# AAA_Battery_Card.net
KiCad netlist of a schematic drawn in EAGLE
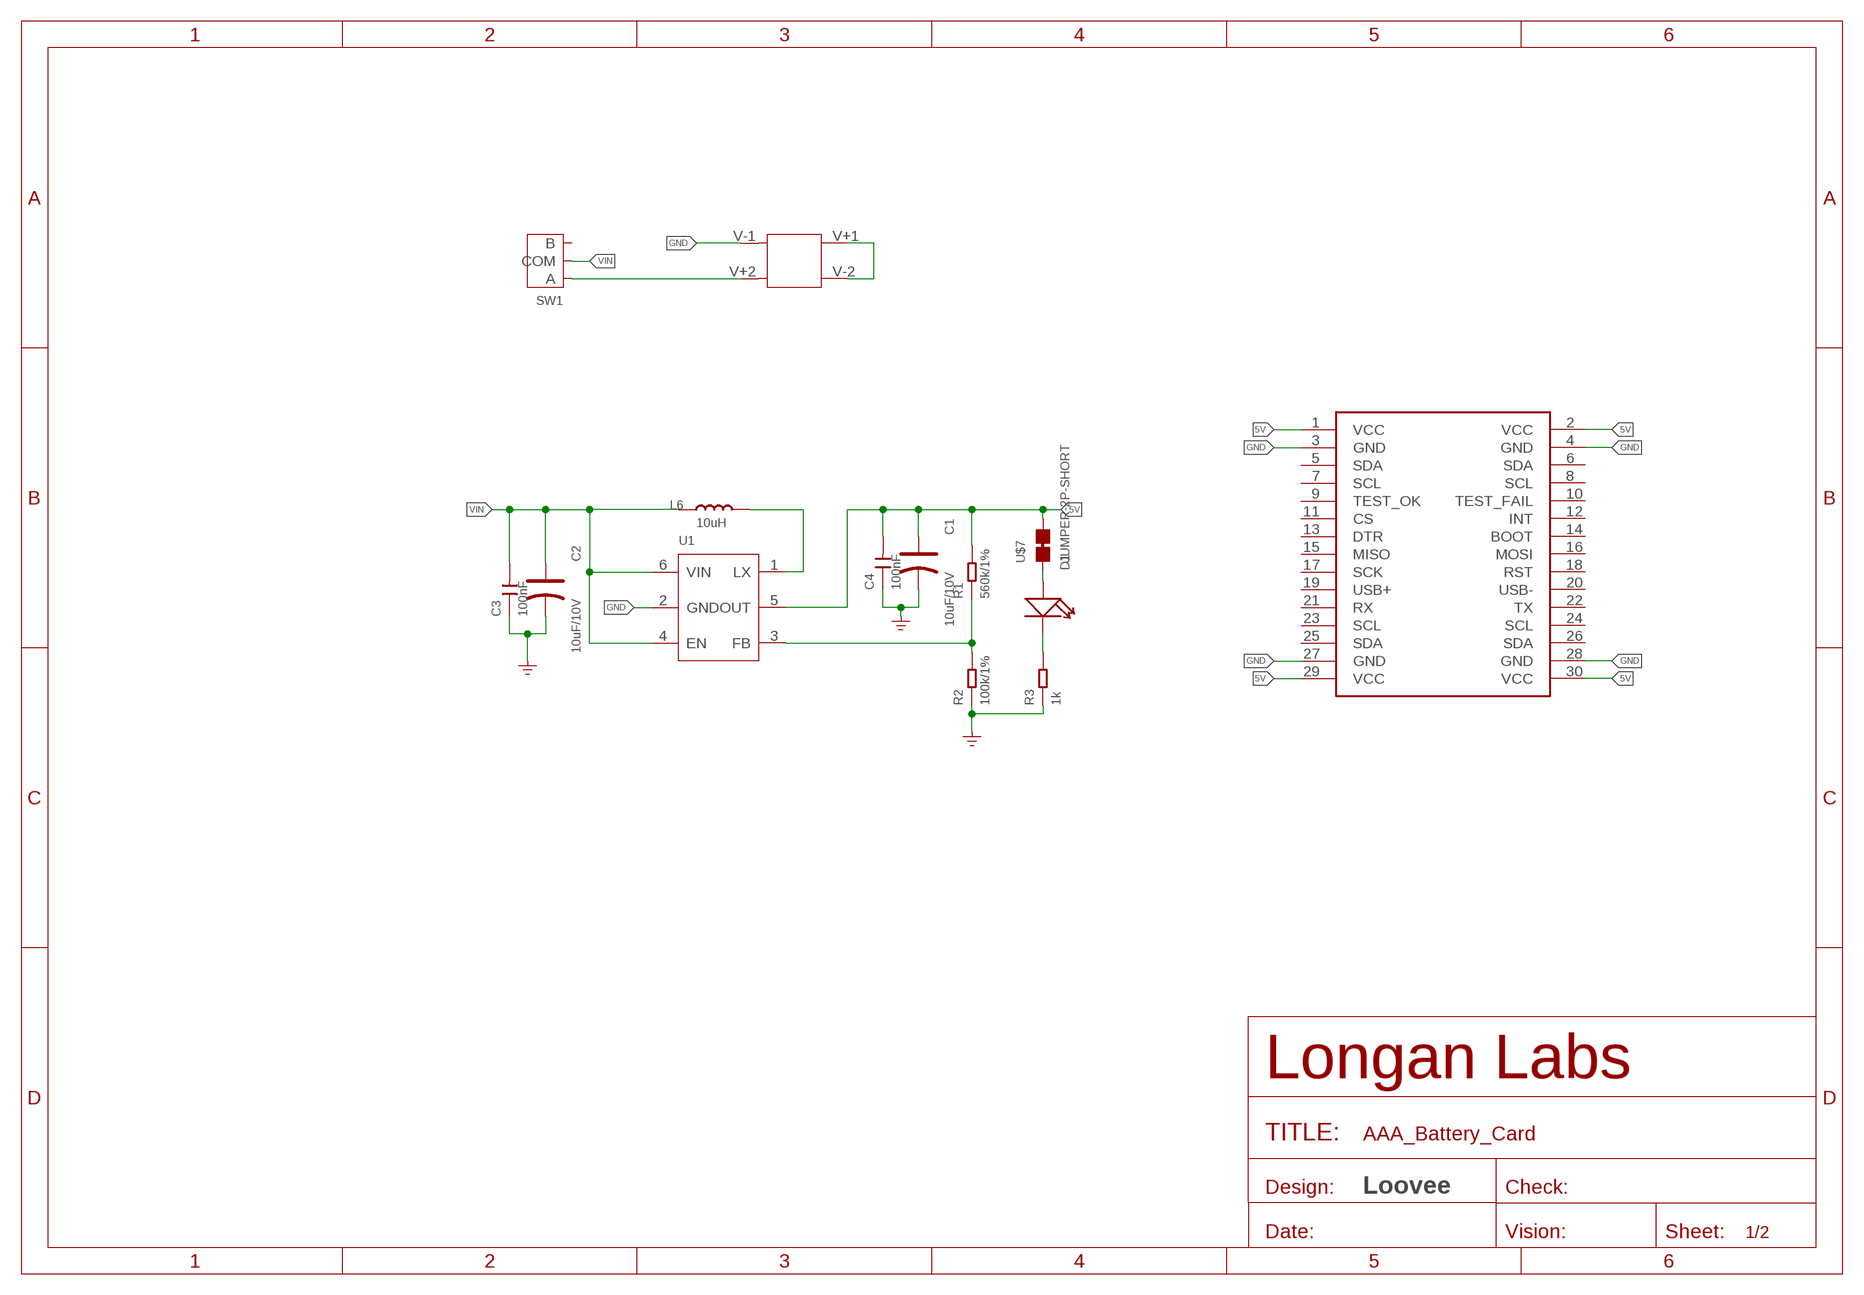
[diagram p0: schematic, sheet 1]

(export (version "E")
  (design (tool "Eeschema 10.0.6"))
  (components
    (comp (ref "BAT1")
      (value "BAT-1.5VX2-HOLDER")
      (footprint "eagle-import:BAT-SMD-54.6X22.4MM")
      (libsource (lib "eagle-import") (part "BAT-1.5VX2-HOLDER"))
    )
    (comp (ref "C1")
      (value "10uF/10V")
      (footprint "eagle-import:AVX-B")
      (libsource (lib "eagle-import") (part "CAP-POLAR-AVX-B"))
    )
    (comp (ref "C2")
      (value "10uF/10V")
      (footprint "eagle-import:AVX-B")
      (libsource (lib "eagle-import") (part "CAP-POLAR-AVX-B"))
    )
    (comp (ref "C3")
      (value "100nF")
      (footprint "eagle-import:C0603")
      (libsource (lib "eagle-import") (part "CAP-0603"))
    )
    (comp (ref "C4")
      (value "100nF")
      (footprint "eagle-import:C0603")
      (libsource (lib "eagle-import") (part "CAP-0603"))
    )
    (comp (ref "D1")
      (value "LED'0603'")
      (footprint "eagle-import:LED-0603")
      (libsource (lib "eagle-import") (part "LED'0603'"))
    )
    (comp (ref "L6")
      (value "10uH")
      (footprint "eagle-import:L0420")
      (libsource (lib "eagle-import") (part "LSPD3D16-4R7M"))
    )
    (comp (ref "MOUDLE1")
      (value "MOUDLE-2X15P-2.54'BOARD'")
      (footprint "eagle-import:MOUDLE-2X15P-2.54")
      (libsource (lib "eagle-import") (part "MOUDLE-2X15P-2.54'BOARD'"))
    )
    (comp (ref "R1")
      (value "560k/1%")
      (footprint "eagle-import:R0603")
      (libsource (lib "eagle-import") (part "RES-0603"))
    )
    (comp (ref "R2")
      (value "100k/1%")
      (footprint "eagle-import:R0603")
      (libsource (lib "eagle-import") (part "RES-0603"))
    )
    (comp (ref "R3")
      (value "1k")
      (footprint "eagle-import:R0603")
      (libsource (lib "eagle-import") (part "RES-0603"))
    )
    (comp (ref "SW1")
      (value "SWITCH-2H-3P")
      (footprint "eagle-import:SW3-2.5-9X3.5MM")
      (libsource (lib "eagle-import") (part "SWITCH-2H-3P"))
    )
    (comp (ref "U$7")
      (value "JUMPER-2P-SHORT")
      (footprint "eagle-import:2P-SMD-SHORT")
      (libsource (lib "eagle-import") (part "JUMPER-2P-SHORT"))
    )
    (comp (ref "U1")
      (value "PMIC-PS7516")
      (footprint "eagle-import:SOT-23-6")
      (libsource (lib "eagle-import") (part "PMIC-PS7516"))
    )
  )
  (nets
    (net (code "1") (name "5V") (class "Default")
      (node (ref "C1") (pin "+") (pinfunction "+_+") (pintype "passive"))
      (node (ref "C4") (pin "2") (pinfunction "2_2") (pintype "passive"))
      (node (ref "MOUDLE1") (pin "1") (pinfunction "VCC_1") (pintype "bidirectional"))
      (node (ref "MOUDLE1") (pin "2") (pinfunction "VCC_2") (pintype "bidirectional"))
      (node (ref "MOUDLE1") (pin "29") (pinfunction "VCC_29") (pintype "bidirectional"))
      (node (ref "MOUDLE1") (pin "30") (pinfunction "VCC_30") (pintype "bidirectional"))
      (node (ref "R1") (pin "2") (pinfunction "2_2") (pintype "passive"))
      (node (ref "U$7") (pin "2") (pinfunction "2_2") (pintype "bidirectional"))
      (node (ref "U1") (pin "5") (pinfunction "OUT_5") (pintype "bidirectional"))
    )
    (net (code "2") (name "GND") (class "Default")
      (node (ref "BAT1") (pin "V-1") (pinfunction "1_V-1") (pintype "bidirectional"))
      (node (ref "C1") (pin "-") (pinfunction "-_-") (pintype "passive"))
      (node (ref "C2") (pin "-") (pinfunction "-_-") (pintype "passive"))
      (node (ref "C3") (pin "1") (pinfunction "1_1") (pintype "passive"))
      (node (ref "C4") (pin "1") (pinfunction "1_1") (pintype "passive"))
      (node (ref "MOUDLE1") (pin "27") (pinfunction "GND_27") (pintype "bidirectional"))
      (node (ref "MOUDLE1") (pin "28") (pinfunction "GND_28") (pintype "bidirectional"))
      (node (ref "MOUDLE1") (pin "3") (pinfunction "GND_3") (pintype "bidirectional"))
      (node (ref "MOUDLE1") (pin "4") (pinfunction "GND_4") (pintype "bidirectional"))
      (node (ref "R2") (pin "1") (pinfunction "1_1") (pintype "passive"))
      (node (ref "R3") (pin "1") (pinfunction "1_1") (pintype "passive"))
      (node (ref "U1") (pin "2") (pinfunction "GND_2") (pintype "bidirectional"))
    )
    (net (code "3") (name "Net-(BAT1-2)") (class "Default")
      (node (ref "BAT1") (pin "V+1") (pinfunction "2_V+1") (pintype "bidirectional"))
      (node (ref "BAT1") (pin "V-2") (pinfunction "4_V-2") (pintype "bidirectional"))
    )
    (net (code "4") (name "Net-(BAT1-3)") (class "Default")
      (node (ref "BAT1") (pin "V+2") (pinfunction "3_V+2") (pintype "bidirectional"))
      (node (ref "SW1") (pin "1") (pinfunction "A_1") (pintype "bidirectional"))
    )
    (net (code "5") (name "Net-(D1-Pad+)") (class "Default")
      (node (ref "D1") (pin "+") (pinfunction "+_+") (pintype "passive"))
      (node (ref "U$7") (pin "1") (pinfunction "1_1") (pintype "bidirectional"))
    )
    (net (code "6") (name "Net-(D1-Pad-)") (class "Default")
      (node (ref "D1") (pin "-") (pinfunction "-_-") (pintype "passive"))
      (node (ref "R3") (pin "2") (pinfunction "2_2") (pintype "passive"))
    )
    (net (code "7") (name "Net-(U1-FB)") (class "Default")
      (node (ref "R1") (pin "1") (pinfunction "1_1") (pintype "passive"))
      (node (ref "R2") (pin "2") (pinfunction "2_2") (pintype "passive"))
      (node (ref "U1") (pin "3") (pinfunction "FB_3") (pintype "bidirectional"))
    )
    (net (code "8") (name "Net-(U1-LX)") (class "Default")
      (node (ref "L6") (pin "2") (pinfunction "2_2") (pintype "passive"))
      (node (ref "U1") (pin "1") (pinfunction "LX_1") (pintype "bidirectional"))
    )
    (net (code "9") (name "VIN") (class "Default")
      (node (ref "C2") (pin "+") (pinfunction "+_+") (pintype "passive"))
      (node (ref "C3") (pin "2") (pinfunction "2_2") (pintype "passive"))
      (node (ref "L6") (pin "1") (pinfunction "1_1") (pintype "passive"))
      (node (ref "SW1") (pin "2") (pinfunction "COM_2") (pintype "bidirectional"))
      (node (ref "U1") (pin "4") (pinfunction "EN_4") (pintype "bidirectional"))
      (node (ref "U1") (pin "6") (pinfunction "VIN_6") (pintype "bidirectional"))
    )
    (net (code "10") (name "unconnected-(MOUDLE1-BOOT-Pad14)") (class "Default")
      (node (ref "MOUDLE1") (pin "14") (pinfunction "BOOT_14") (pintype "bidirectional"))
    )
    (net (code "11") (name "unconnected-(MOUDLE1-CS-Pad11)") (class "Default")
      (node (ref "MOUDLE1") (pin "11") (pinfunction "CS_11") (pintype "bidirectional"))
    )
    (net (code "12") (name "unconnected-(MOUDLE1-DTR-Pad13)") (class "Default")
      (node (ref "MOUDLE1") (pin "13") (pinfunction "DTR_13") (pintype "bidirectional"))
    )
    (net (code "13") (name "unconnected-(MOUDLE1-INT-Pad12)") (class "Default")
      (node (ref "MOUDLE1") (pin "12") (pinfunction "INT_12") (pintype "bidirectional"))
    )
    (net (code "14") (name "unconnected-(MOUDLE1-MISO-Pad15)") (class "Default")
      (node (ref "MOUDLE1") (pin "15") (pinfunction "MISO_15") (pintype "bidirectional"))
    )
    (net (code "15") (name "unconnected-(MOUDLE1-MOSI-Pad16)") (class "Default")
      (node (ref "MOUDLE1") (pin "16") (pinfunction "MOSI_16") (pintype "bidirectional"))
    )
    (net (code "16") (name "unconnected-(MOUDLE1-RST-Pad18)") (class "Default")
      (node (ref "MOUDLE1") (pin "18") (pinfunction "RST_18") (pintype "bidirectional"))
    )
    (net (code "17") (name "unconnected-(MOUDLE1-RX-Pad21)") (class "Default")
      (node (ref "MOUDLE1") (pin "21") (pinfunction "RX_21") (pintype "bidirectional"))
    )
    (net (code "18") (name "unconnected-(MOUDLE1-SCK-Pad17)") (class "Default")
      (node (ref "MOUDLE1") (pin "17") (pinfunction "SCK_17") (pintype "bidirectional"))
    )
    (net (code "19") (name "unconnected-(MOUDLE1-SCL-Pad7)") (class "Default")
      (node (ref "MOUDLE1") (pin "7") (pinfunction "SCL_7") (pintype "bidirectional"))
    )
    (net (code "20") (name "unconnected-(MOUDLE1-SCL-Pad8)") (class "Default")
      (node (ref "MOUDLE1") (pin "8") (pinfunction "SCL_8") (pintype "bidirectional"))
    )
    (net (code "21") (name "unconnected-(MOUDLE1-SCL-Pad23)") (class "Default")
      (node (ref "MOUDLE1") (pin "23") (pinfunction "SCL_23") (pintype "bidirectional"))
    )
    (net (code "22") (name "unconnected-(MOUDLE1-SCL-Pad24)") (class "Default")
      (node (ref "MOUDLE1") (pin "24") (pinfunction "SCL_24") (pintype "bidirectional"))
    )
    (net (code "23") (name "unconnected-(MOUDLE1-SDA-Pad5)") (class "Default")
      (node (ref "MOUDLE1") (pin "5") (pinfunction "SDA_5") (pintype "bidirectional"))
    )
    (net (code "24") (name "unconnected-(MOUDLE1-SDA-Pad6)") (class "Default")
      (node (ref "MOUDLE1") (pin "6") (pinfunction "SDA_6") (pintype "bidirectional"))
    )
    (net (code "25") (name "unconnected-(MOUDLE1-SDA-Pad25)") (class "Default")
      (node (ref "MOUDLE1") (pin "25") (pinfunction "SDA_25") (pintype "bidirectional"))
    )
    (net (code "26") (name "unconnected-(MOUDLE1-SDA-Pad26)") (class "Default")
      (node (ref "MOUDLE1") (pin "26") (pinfunction "SDA_26") (pintype "bidirectional"))
    )
    (net (code "27") (name "unconnected-(MOUDLE1-TEST_FAIL-Pad10)") (class "Default")
      (node (ref "MOUDLE1") (pin "10") (pinfunction "TEST_FAIL_10") (pintype "bidirectional"))
    )
    (net (code "28") (name "unconnected-(MOUDLE1-TEST_OK-Pad9)") (class "Default")
      (node (ref "MOUDLE1") (pin "9") (pinfunction "TEST_OK_9") (pintype "bidirectional"))
    )
    (net (code "29") (name "unconnected-(MOUDLE1-TX-Pad22)") (class "Default")
      (node (ref "MOUDLE1") (pin "22") (pinfunction "TX_22") (pintype "bidirectional"))
    )
    (net (code "30") (name "unconnected-(MOUDLE1-USB+-Pad19)") (class "Default")
      (node (ref "MOUDLE1") (pin "19") (pinfunction "USB+_19") (pintype "bidirectional"))
    )
    (net (code "31") (name "unconnected-(MOUDLE1-USB--Pad20)") (class "Default")
      (node (ref "MOUDLE1") (pin "20") (pinfunction "USB-_20") (pintype "bidirectional"))
    )
    (net (code "32") (name "unconnected-(SW1-B-Pad3)") (class "Default")
      (node (ref "SW1") (pin "3") (pinfunction "B_3") (pintype "bidirectional"))
    )
  )
)
